# 12_4.net
KiCad netlist of a schematic drawn in Altium Designer
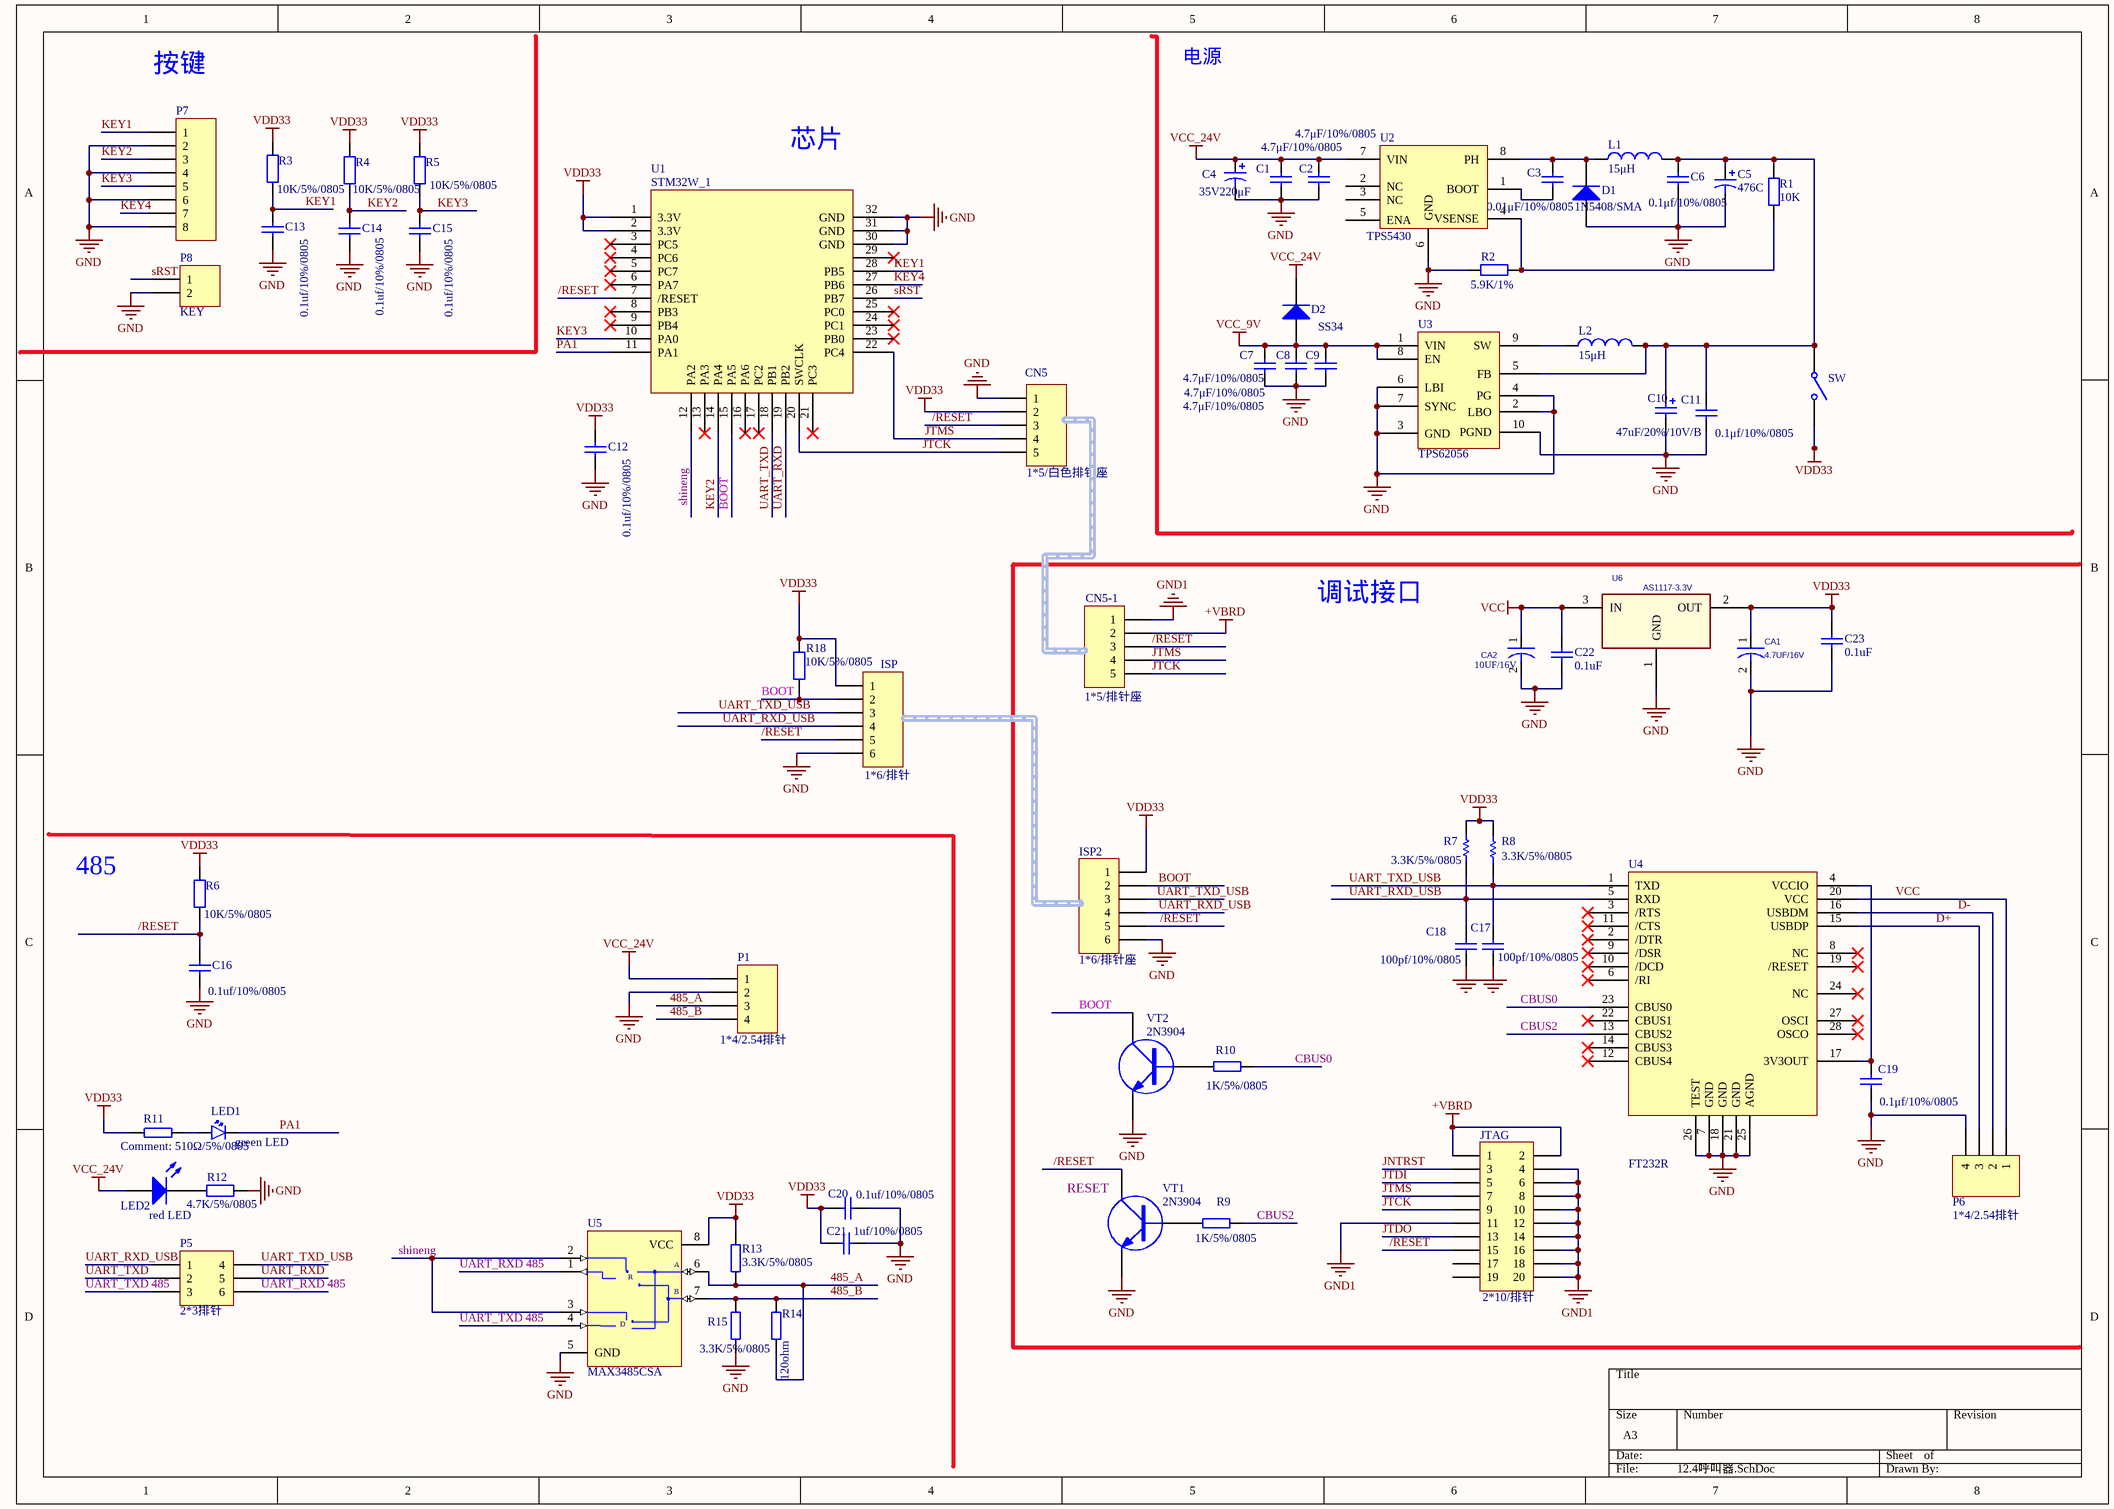
[diagram p0: 12.4呼叫器.SchDoc]

(export (version "E")
  (design (tool "Eeschema 10.0.6"))
  (components
    (comp (ref "C1")
      (value "4.7μF/10%/0805")
      (footprint "C-0805")
      (description "Capacitor")
      (fields (field (name "PUBLISHER") "Altium Limited"))
      (libsource (lib "Miscellaneous Devices") (part "Cap"))
    )
    (comp (ref "C2")
      (value "4.7μF/10%/0805")
      (footprint "C-0805")
      (description "Capacitor")
      (fields (field (name "PUBLISHER") "Altium Limited"))
      (libsource (lib "Miscellaneous Devices") (part "Cap"))
    )
    (comp (ref "C3")
      (value "0.01μF/10%/0805")
      (footprint "C-0805")
      (description "Capacitor")
      (fields (field (name "PUBLISHER") "Altium Limited"))
      (libsource (lib "Miscellaneous Devices") (part "Cap"))
    )
    (comp (ref "C4")
      (value "35V220μF")
      (footprint "CZ3.0/6.5")
      (description "Polarized Capacitor (Radial)")
      (fields (field (name "PUBLISHER") "Altium Limited"))
      (libsource (lib "Miscellaneous Devices") (part "Cap Pol1"))
    )
    (comp (ref "C5")
      (value "476C")
      (footprint "C-TAN-D")
      (description "Polarized Capacitor (Radial)")
      (fields (field (name "PUBLISHER") "Altium Limited"))
      (libsource (lib "Miscellaneous Devices") (part "Cap Pol1"))
    )
    (comp (ref "C6")
      (value "0.1μf/10%/0805")
      (footprint "C-0805")
      (description "Capacitor")
      (fields (field (name "PUBLISHER") "Altium Limited"))
      (libsource (lib "Miscellaneous Devices") (part "Cap"))
    )
    (comp (ref "C7")
      (value "4.7μF/10%/0805")
      (footprint "C-0805")
      (description "Capacitor")
      (fields (field (name "PUBLISHER") "Altium Limited"))
      (libsource (lib "Miscellaneous Devices") (part "Cap"))
    )
    (comp (ref "C8")
      (value "4.7μF/10%/0805")
      (footprint "C-0805")
      (description "Capacitor")
      (fields (field (name "PUBLISHER") "Altium Limited"))
      (libsource (lib "Miscellaneous Devices") (part "Cap"))
    )
    (comp (ref "C9")
      (value "4.7μF/10%/0805")
      (footprint "C-0805")
      (description "Capacitor")
      (fields (field (name "PUBLISHER") "Altium Limited"))
      (libsource (lib "Miscellaneous Devices") (part "Cap"))
    )
    (comp (ref "C10")
      (value "47uF/20%/10V/B")
      (footprint "C-TAN-B")
      (libsource (lib "浙江关西电机数据库") (part "CAP_polarity"))
    )
    (comp (ref "C11")
      (value "0.1μf/10%/0805")
      (footprint "C-0805")
      (description "Capacitor")
      (fields (field (name "PUBLISHER") "Altium Limited"))
      (libsource (lib "Miscellaneous Devices") (part "Cap"))
    )
    (comp (ref "C12")
      (value "0.1uf/10%/0805")
      (footprint "C-0805")
      (description "Capacitor")
      (fields (field (name "PUBLISHER") "Altium Limited"))
      (libsource (lib "Miscellaneous Devices") (part "Cap"))
    )
    (comp (ref "C13")
      (value "0.1uf/10%/0805")
      (footprint "C-0805")
      (description "Capacitor")
      (fields (field (name "PUBLISHER") "Altium Limited"))
      (libsource (lib "Miscellaneous Devices") (part "Cap"))
    )
    (comp (ref "C14")
      (value "0.1uf/10%/0805")
      (footprint "C-0805")
      (description "Capacitor")
      (fields (field (name "PUBLISHER") "Altium Limited"))
      (libsource (lib "Miscellaneous Devices") (part "Cap"))
    )
    (comp (ref "C15")
      (value "0.1uf/10%/0805")
      (footprint "C-0805")
      (description "Capacitor")
      (fields (field (name "PUBLISHER") "Altium Limited"))
      (libsource (lib "Miscellaneous Devices") (part "Cap"))
    )
    (comp (ref "C16")
      (value "0.1uf/10%/0805")
      (footprint "C-0805")
      (description "Capacitor")
      (fields (field (name "PUBLISHER") "Altium Limited"))
      (libsource (lib "Miscellaneous Devices") (part "Cap"))
    )
    (comp (ref "C17")
      (value "100pf/10%/0805")
      (footprint "C-0805")
      (description "Capacitor")
      (fields (field (name "PUBLISHER") "Altium Limited"))
      (libsource (lib "Miscellaneous Devices") (part "Cap"))
    )
    (comp (ref "C18")
      (value "100pf/10%/0805")
      (footprint "C-0805")
      (description "Capacitor")
      (fields (field (name "PUBLISHER") "Altium Limited"))
      (libsource (lib "Miscellaneous Devices") (part "Cap"))
    )
    (comp (ref "C19")
      (value "0.1μf/10%/0805")
      (footprint "C-0805")
      (description "Capacitor")
      (fields (field (name "PUBLISHER") "Altium Limited"))
      (libsource (lib "Miscellaneous Devices") (part "Cap"))
    )
    (comp (ref "C20")
      (value "0.1uf/10%/0805")
      (footprint "C-0805")
      (description "Capacitor")
      (fields (field (name "PUBLISHER") "Altium Limited"))
      (libsource (lib "Miscellaneous Devices") (part "Cap"))
    )
    (comp (ref "C21")
      (value "1uf/10%/0805")
      (footprint "C-0805")
      (description "Capacitor")
      (fields (field (name "PUBLISHER") "Altium Limited"))
      (libsource (lib "Miscellaneous Devices") (part "Cap"))
    )
    (comp (ref "C22")
      (value "0.1uF")
      (footprint "C0805")
      (description "Capacitor")
      (fields (field (name "PUBLISHER") "Altium Limited"))
      (libsource (lib "Miscellaneous Devices") (part "Cap"))
    )
    (comp (ref "C23")
      (value "0.1uF")
      (footprint "C0805")
      (description "Capacitor")
      (fields (field (name "PUBLISHER") "Altium Limited"))
      (libsource (lib "Miscellaneous Devices") (part "Cap"))
    )
    (comp (ref "CA1") (value "4.7UF/16V") (footprint "3528") (libsource (lib "v3") (part "ECAP")))
    (comp (ref "CA2") (value "10UF/16V") (footprint "3528") (libsource (lib "v3") (part "ECAP")))
    (comp (ref "CN5")
      (value "1*5/白色排针座")
      (footprint "PIN-S-2.54-1*5")
      (libsource (lib "SCHLIBRARIES") (part "Header1*5"))
    )
    (comp (ref "CN5-1")
      (value "1*5/排针座")
      (footprint "PIN-S-2.54-1*5")
      (libsource (lib "") (part "Header1*5_1"))
    )
    (comp (ref "D1")
      (value "1N5408/SMA")
      (footprint "SMA 2+")
      (description "3 Amp Medium Power Silicon Rectifier Diode")
      (fields (field (name "PUBLISHER") "Altium Limited"))
      (libsource (lib "Miscellaneous Devices") (part "Diode 1N5408"))
    )
    (comp (ref "D2")
      (value "SS34")
      (footprint "smb")
      (description "3 Amp Medium Power Silicon Rectifier Diode")
      (fields (field (name "PUBLISHER") "Altium Limited"))
      (libsource (lib "Miscellaneous Devices") (part "Diode 1N5408"))
    )
    (comp (ref "ISP") (value "1*6/排针") (footprint "PIN-S-2.54-1*6") (libsource (lib "") (part "Header1*6_1")))
    (comp (ref "ISP2")
      (value "1*6/排针座")
      (footprint "PIN-S-2.54-1*6")
      (libsource (lib "SCHLIBRARIES") (part "Header1*6"))
    )
    (comp (ref "JTAG")
      (value "2*10/排针")
      (footprint "IDC-20")
      (libsource (lib "SCHLIBRARIES") (part "Header2*10"))
    )
    (comp (ref "L1")
      (value "15μH")
      (footprint "GSDS104C2")
      (description "Inductor")
      (fields (field (name "PUBLISHER") "Altium Limited"))
      (libsource (lib "Miscellaneous Devices") (part "Inductor"))
    )
    (comp (ref "L2")
      (value "15μH")
      (footprint "GSDS104C2")
      (description "Inductor")
      (fields (field (name "PUBLISHER") "Altium Limited"))
      (libsource (lib "Miscellaneous Devices") (part "Inductor"))
    )
    (comp (ref "LED1") (value "green LED") (footprint "LED-φ3") (libsource (lib "Haze") (part "LED")))
    (comp (ref "LED2")
      (value "red LED")
      (footprint "LED-φ3")
      (description "Typical BLUE SiC LED")
      (fields (field (name "PUBLISHER") "Altium Limited"))
      (libsource (lib "Miscellaneous Devices") (part "LED3"))
    )
    (comp (ref "P1")
      (value "1*4/2.54排针")
      (footprint "PIN-S-2.54-1*4")
      (description "Header, 4-Pin")
      (fields (field (name "PUBLISHER") "Altium Limited"))
      (libsource (lib "Miscellaneous Connectors") (part "Header 4"))
    )
    (comp (ref "P5")
      (value "2*3排针")
      (footprint "HDR2X3_CEN")
      (description "Header, 3-Pin, Dual row")
      (fields (field (name "PUBLISHER") "Altium Limited"))
      (libsource (lib "Miscellaneous Connectors") (part "Header 3X2A"))
    )
    (comp (ref "P6")
      (value "1*4/2.54排针")
      (footprint "USB_B_90D")
      (description "Header, 4-Pin")
      (fields (field (name "PUBLISHER") "Altium Limited"))
      (libsource (lib "") (part "Header 4_1"))
    )
    (comp (ref "P7")
      (value "Header 8")
      (footprint "HDR1X8")
      (description "Header, 8-Pin")
      (fields (field (name "PUBLISHER") "Altium Limited"))
      (libsource (lib "Miscellaneous Connectors") (part "Header 8"))
    )
    (comp (ref "P8")
      (value "KEY")
      (footprint "KEY-DIP")
      (description "Header, 2-Pin")
      (fields (field (name "PUBLISHER") "Altium Limited"))
      (libsource (lib "Miscellaneous Connectors") (part "Header 2"))
    )
    (comp (ref "R1")
      (value "10K")
      (footprint "R-0805")
      (description "Resistor")
      (fields (field (name "PUBLISHER") "Altium Limited"))
      (libsource (lib "Miscellaneous Devices") (part "Res2"))
    )
    (comp (ref "R2")
      (value "5.9K/1%")
      (footprint "R-0805")
      (description "Resistor")
      (fields (field (name "PUBLISHER") "Altium Limited"))
      (libsource (lib "") (part "Res2_1"))
    )
    (comp (ref "R3")
      (value "10K/5%/0805")
      (footprint "R-0805")
      (description "Resistor")
      (fields (field (name "PUBLISHER") "Altium Limited"))
      (libsource (lib "Miscellaneous Devices") (part "Res2"))
    )
    (comp (ref "R4")
      (value "10K/5%/0805")
      (footprint "R-0805")
      (description "Resistor")
      (fields (field (name "PUBLISHER") "Altium Limited"))
      (libsource (lib "Miscellaneous Devices") (part "Res2"))
    )
    (comp (ref "R5")
      (value "10K/5%/0805")
      (footprint "R-0805")
      (description "Resistor")
      (fields (field (name "PUBLISHER") "Altium Limited"))
      (libsource (lib "Miscellaneous Devices") (part "Res2"))
    )
    (comp (ref "R6")
      (value "10K/5%/0805")
      (footprint "R-0805")
      (description "Resistor")
      (fields (field (name "PUBLISHER") "Altium Limited"))
      (libsource (lib "Miscellaneous Devices") (part "Res2"))
    )
    (comp (ref "R7")
      (value "3.3K/5%/0805")
      (footprint "R-0805")
      (libsource (lib "SCHLIBRARIES") (part "RES_1"))
    )
    (comp (ref "R8")
      (value "3.3K/5%/0805")
      (footprint "R-0805")
      (libsource (lib "SCHLIBRARIES") (part "RES_1"))
    )
    (comp (ref "R9")
      (value "1K/5%/0805")
      (footprint "R-0805")
      (description "R")
      (libsource (lib "Haze") (part "RES"))
    )
    (comp (ref "R10")
      (value "1K/5%/0805")
      (footprint "R-0805")
      (description "R")
      (libsource (lib "Haze") (part "RES"))
    )
    (comp (ref "R11")
      (value "510Ω/5%/0805")
      (footprint "R-0805")
      (description "R")
      (libsource (lib "Haze") (part "RES"))
    )
    (comp (ref "R12")
      (value "4.7K/5%/0805")
      (footprint "R-0805")
      (description "Resistor")
      (fields (field (name "PUBLISHER") "Altium Limited"))
      (libsource (lib "") (part "Res2_1"))
    )
    (comp (ref "R13")
      (value "3.3K/5%/0805")
      (footprint "R-0805")
      (description "R")
      (libsource (lib "Haze") (part "RES"))
    )
    (comp (ref "R14")
      (value "120ohm")
      (footprint "R-0805")
      (description "R")
      (libsource (lib "Haze") (part "RES"))
    )
    (comp (ref "R15")
      (value "3.3K/5%/0805")
      (footprint "R-0805")
      (description "R")
      (libsource (lib "Haze") (part "RES"))
    )
    (comp (ref "R18")
      (value "10K/5%/0805")
      (footprint "R-0805")
      (description "Resistor")
      (fields (field (name "PUBLISHER") "Altium Limited"))
      (libsource (lib "Miscellaneous Devices") (part "Res2"))
    )
    (comp (ref "SW")
      (value "SW-1")
      (footprint "PIN-S-2.54-1*2")
      (libsource (lib "SCHLIBRARIES") (part "SW-1"))
    )
    (comp (ref "U1")
      (value "STM32W_1")
      (footprint "STM32W108-3")
      (libsource (lib "STM32W108-3") (part "STM32W108-3"))
    )
    (comp (ref "U2") (value "TPS5430") (footprint "SO-G8") (libsource (lib "SCHLIBRARIES") (part "TPS5430")))
    (comp (ref "U3")
      (value "TPS62056")
      (footprint "MSOP-10")
      (libsource (lib "SCHLIBRARIES") (part "TPS62056"))
    )
    (comp (ref "U4") (value "FT232R") (footprint "SSOP-28") (libsource (lib "Haze") (part "FT232R")))
    (comp (ref "U5")
      (value "MAX3485CSA")
      (footprint "SO-G8")
      (description "Low-Power, Slew-Rate-Limited RS-485/RS-422 Transceiver")
      (fields (field (name "PUBLISHER") "Altium Limited"))
      (libsource (lib "Maxim Communication Transceiver") (part "MAX485CSA"))
    )
    (comp (ref "U6") (value "AS1117-3.3V") (libsource (lib "v3") (part "AS1117")))
    (comp (ref "VT1")
      (value "2N3904")
      (footprint "SOT23-3")
      (description "NPN Transistor")
      (libsource (lib "Haze") (part "NPN"))
    )
    (comp (ref "VT2")
      (value "2N3904")
      (footprint "SOT23-3")
      (description "NPN Transistor")
      (libsource (lib "Haze") (part "NPN"))
    )
  )
  (nets
    (net (code "1") (name "+VBRD") (class "Default")
      (node (ref "CN5-1") (pin "2") (pinfunction "2_2") (pintype "passive"))
      (node (ref "JTAG") (pin "1") (pinfunction "1_1") (pintype "passive"))
      (node (ref "JTAG") (pin "2") (pinfunction "2_2") (pintype "passive"))
    )
    (net (code "2") (name "/485_A") (class "Default")
      (node (ref "P1") (pin "3") (pinfunction "3_3") (pintype "passive"))
      (node (ref "R13") (pin "1") (pinfunction "1_1") (pintype "passive"))
      (node (ref "R14") (pin "2") (pinfunction "2_2") (pintype "passive"))
      (node (ref "U5") (pin "6") (pinfunction "A_6") (pintype "bidirectional"))
    )
    (net (code "3") (name "/485_B") (class "Default")
      (node (ref "P1") (pin "4") (pinfunction "4_4") (pintype "passive"))
      (node (ref "R14") (pin "1") (pinfunction "1_1") (pintype "passive"))
      (node (ref "R15") (pin "2") (pinfunction "2_2") (pintype "passive"))
      (node (ref "U5") (pin "7") (pinfunction "B_7") (pintype "bidirectional"))
    )
    (net (code "4") (name "/BOOT") (class "Default")
      (node (ref "ISP") (pin "2") (pinfunction "2_2") (pintype "passive"))
      (node (ref "ISP2") (pin "2") (pinfunction "2_2") (pintype "passive"))
      (node (ref "R18") (pin "1") (pinfunction "1_1") (pintype "passive"))
      (node (ref "U1") (pin "15") (pinfunction "PA5_15") (pintype "passive"))
      (node (ref "VT2") (pin "3") (pinfunction "C_3") (pintype "passive"))
    )
    (net (code "5") (name "/CBUS0") (class "Default")
      (node (ref "R10") (pin "2") (pinfunction "2_2") (pintype "passive"))
      (node (ref "U4") (pin "23") (pinfunction "CBUS0_23") (pintype "passive"))
    )
    (net (code "6") (name "/CBUS2") (class "Default")
      (node (ref "R9") (pin "2") (pinfunction "2_2") (pintype "passive"))
      (node (ref "U4") (pin "13") (pinfunction "CBUS2_13") (pintype "passive"))
    )
    (net (code "7") (name "/D+") (class "Default")
      (node (ref "P6") (pin "3") (pinfunction "3_3") (pintype "passive"))
      (node (ref "U4") (pin "15") (pinfunction "USBDP_15") (pintype "passive"))
    )
    (net (code "8") (name "/D-") (class "Default")
      (node (ref "P6") (pin "2") (pinfunction "2_2") (pintype "passive"))
      (node (ref "U4") (pin "16") (pinfunction "USBDM_16") (pintype "passive"))
    )
    (net (code "9") (name "/JNTRST") (class "Default")
      (node (ref "JTAG") (pin "3") (pinfunction "3_3") (pintype "passive"))
    )
    (net (code "10") (name "/JTCK") (class "Default")
      (node (ref "CN5") (pin "5") (pinfunction "5_5") (pintype "passive"))
      (node (ref "CN5-1") (pin "5") (pinfunction "5_5") (pintype "passive"))
      (node (ref "JTAG") (pin "9") (pinfunction "9_9") (pintype "passive"))
      (node (ref "U1") (pin "20") (pinfunction "SWCLK_20") (pintype "passive"))
    )
    (net (code "11") (name "/JTDI") (class "Default")
      (node (ref "JTAG") (pin "5") (pinfunction "5_5") (pintype "passive"))
    )
    (net (code "12") (name "/JTDO") (class "Default")
      (node (ref "JTAG") (pin "13") (pinfunction "13_13") (pintype "passive"))
    )
    (net (code "13") (name "/JTMS") (class "Default")
      (node (ref "CN5") (pin "4") (pinfunction "4_4") (pintype "passive"))
      (node (ref "CN5-1") (pin "4") (pinfunction "4_4") (pintype "passive"))
      (node (ref "JTAG") (pin "7") (pinfunction "7_7") (pintype "passive"))
      (node (ref "U1") (pin "22") (pinfunction "PC4_22") (pintype "passive"))
    )
    (net (code "14") (name "/KEY1") (class "Default")
      (node (ref "C13") (pin "2") (pinfunction "2_2") (pintype "passive"))
      (node (ref "P7") (pin "1") (pinfunction "1_1") (pintype "passive"))
      (node (ref "R3") (pin "1") (pinfunction "1_1") (pintype "passive"))
      (node (ref "U1") (pin "28") (pinfunction "PB5_28") (pintype "passive"))
    )
    (net (code "15") (name "/KEY2") (class "Default")
      (node (ref "C14") (pin "2") (pinfunction "2_2") (pintype "passive"))
      (node (ref "P7") (pin "3") (pinfunction "3_3") (pintype "passive"))
      (node (ref "R4") (pin "1") (pinfunction "1_1") (pintype "passive"))
      (node (ref "U1") (pin "14") (pinfunction "PA4_14") (pintype "passive"))
    )
    (net (code "16") (name "/KEY3") (class "Default")
      (node (ref "C15") (pin "2") (pinfunction "2_2") (pintype "passive"))
      (node (ref "P7") (pin "5") (pinfunction "5_5") (pintype "passive"))
      (node (ref "R5") (pin "1") (pinfunction "1_1") (pintype "passive"))
      (node (ref "U1") (pin "10") (pinfunction "PA0_10") (pintype "passive"))
    )
    (net (code "17") (name "/KEY4") (class "Default")
      (node (ref "P7") (pin "7") (pinfunction "7_7") (pintype "passive"))
      (node (ref "U1") (pin "27") (pinfunction "PB6_27") (pintype "passive"))
    )
    (net (code "18") (name "/PA1") (class "Default")
      (node (ref "LED1") (pin "2") (pinfunction "K_2") (pintype "passive"))
      (node (ref "U1") (pin "11") (pinfunction "PA1_11") (pintype "passive"))
    )
    (net (code "19") (name "/UART_RXD") (class "Default")
      (node (ref "P5") (pin "5") (pinfunction "5_5") (pintype "passive"))
      (node (ref "U1") (pin "19") (pinfunction "PB2_19") (pintype "passive"))
    )
    (net (code "20") (name "/UART_RXD 485") (class "Default")
      (node (ref "P5") (pin "6") (pinfunction "6_6") (pintype "passive"))
      (node (ref "U5") (pin "1") (pinfunction "RO_1") (pintype "output"))
    )
    (net (code "21") (name "/UART_RXD_USB") (class "Default")
      (node (ref "C18") (pin "2") (pinfunction "2_2") (pintype "passive"))
      (node (ref "ISP") (pin "4") (pinfunction "4_4") (pintype "passive"))
      (node (ref "ISP2") (pin "4") (pinfunction "4_4") (pintype "passive"))
      (node (ref "P5") (pin "1") (pinfunction "1_1") (pintype "passive"))
      (node (ref "R7") (pin "1") (pinfunction "1_1") (pintype "passive"))
      (node (ref "U4") (pin "5") (pinfunction "RXD_5") (pintype "passive"))
    )
    (net (code "22") (name "/UART_TXD") (class "Default")
      (node (ref "P5") (pin "2") (pinfunction "2_2") (pintype "passive"))
      (node (ref "U1") (pin "18") (pinfunction "PB1_18") (pintype "passive"))
    )
    (net (code "23") (name "/UART_TXD 485") (class "Default")
      (node (ref "P5") (pin "3") (pinfunction "3_3") (pintype "passive"))
      (node (ref "U5") (pin "4") (pinfunction "DI_4") (pintype "input"))
    )
    (net (code "24") (name "/UART_TXD_USB") (class "Default")
      (node (ref "C17") (pin "2") (pinfunction "2_2") (pintype "passive"))
      (node (ref "ISP") (pin "3") (pinfunction "3_3") (pintype "passive"))
      (node (ref "ISP2") (pin "3") (pinfunction "3_3") (pintype "passive"))
      (node (ref "P5") (pin "4") (pinfunction "4_4") (pintype "passive"))
      (node (ref "R8") (pin "1") (pinfunction "1_1") (pintype "passive"))
      (node (ref "U4") (pin "1") (pinfunction "TXD_1") (pintype "passive"))
    )
    (net (code "25") (name "/sRST") (class "Default")
      (node (ref "P8") (pin "1") (pinfunction "1_1") (pintype "passive"))
      (node (ref "U1") (pin "26") (pinfunction "PB7_26") (pintype "passive"))
    )
    (net (code "26") (name "/shineng") (class "Default")
      (node (ref "U1") (pin "12") (pinfunction "PA2_12") (pintype "passive"))
      (node (ref "U5") (pin "2") (pinfunction "~{RE}_2") (pintype "input"))
      (node (ref "U5") (pin "3") (pinfunction "DE_3") (pintype "input"))
    )
    (net (code "27") (name "/{slash}RESET") (class "Default")
      (node (ref "C16") (pin "2") (pinfunction "2_2") (pintype "passive"))
      (node (ref "CN5") (pin "3") (pinfunction "3_3") (pintype "passive"))
      (node (ref "CN5-1") (pin "3") (pinfunction "3_3") (pintype "passive"))
      (node (ref "ISP") (pin "5") (pinfunction "5_5") (pintype "passive"))
      (node (ref "ISP2") (pin "5") (pinfunction "5_5") (pintype "passive"))
      (node (ref "JTAG") (pin "15") (pinfunction "15_15") (pintype "passive"))
      (node (ref "R6") (pin "1") (pinfunction "1_1") (pintype "passive"))
      (node (ref "U1") (pin "7") (pinfunction "/RESET_7") (pintype "passive"))
      (node (ref "VT1") (pin "3") (pinfunction "C_3") (pintype "passive"))
    )
    (net (code "28") (name "GND") (class "Default")
      (node (ref "C1") (pin "1") (pinfunction "1_1") (pintype "passive"))
      (node (ref "C10") (pin "2") (pinfunction "2_2") (pintype "passive"))
      (node (ref "C11") (pin "1") (pinfunction "1_1") (pintype "passive"))
      (node (ref "C12") (pin "1") (pinfunction "1_1") (pintype "passive"))
      (node (ref "C13") (pin "1") (pinfunction "1_1") (pintype "passive"))
      (node (ref "C14") (pin "1") (pinfunction "1_1") (pintype "passive"))
      (node (ref "C15") (pin "1") (pinfunction "1_1") (pintype "passive"))
      (node (ref "C16") (pin "1") (pinfunction "1_1") (pintype "passive"))
      (node (ref "C17") (pin "1") (pinfunction "1_1") (pintype "passive"))
      (node (ref "C18") (pin "1") (pinfunction "1_1") (pintype "passive"))
      (node (ref "C19") (pin "1") (pinfunction "1_1") (pintype "passive"))
      (node (ref "C2") (pin "1") (pinfunction "1_1") (pintype "passive"))
      (node (ref "C20") (pin "1") (pinfunction "1_1") (pintype "passive"))
      (node (ref "C21") (pin "1") (pinfunction "1_1") (pintype "passive"))
      (node (ref "C22") (pin "1") (pinfunction "1_1") (pintype "passive"))
      (node (ref "C23") (pin "1") (pinfunction "1_1") (pintype "passive"))
      (node (ref "C4") (pin "2") (pinfunction "2_2") (pintype "passive"))
      (node (ref "C5") (pin "2") (pinfunction "2_2") (pintype "passive"))
      (node (ref "C6") (pin "1") (pinfunction "1_1") (pintype "passive"))
      (node (ref "C7") (pin "1") (pinfunction "1_1") (pintype "passive"))
      (node (ref "C8") (pin "1") (pinfunction "1_1") (pintype "passive"))
      (node (ref "C9") (pin "1") (pinfunction "1_1") (pintype "passive"))
      (node (ref "CA1") (pin "2") (pinfunction "2_2") (pintype "passive"))
      (node (ref "CA2") (pin "2") (pinfunction "2_2") (pintype "passive"))
      (node (ref "CN5") (pin "1") (pinfunction "1_1") (pintype "passive"))
      (node (ref "D1") (pin "1") (pinfunction "A_1") (pintype "passive"))
      (node (ref "ISP") (pin "6") (pinfunction "6_6") (pintype "passive"))
      (node (ref "ISP2") (pin "6") (pinfunction "6_6") (pintype "passive"))
      (node (ref "P1") (pin "2") (pinfunction "2_2") (pintype "passive"))
      (node (ref "P6") (pin "4") (pinfunction "4_4") (pintype "passive"))
      (node (ref "P7") (pin "2") (pinfunction "2_2") (pintype "passive"))
      (node (ref "P7") (pin "4") (pinfunction "4_4") (pintype "passive"))
      (node (ref "P7") (pin "6") (pinfunction "6_6") (pintype "passive"))
      (node (ref "P7") (pin "8") (pinfunction "8_8") (pintype "passive"))
      (node (ref "P8") (pin "2") (pinfunction "2_2") (pintype "passive"))
      (node (ref "R12") (pin "1") (pinfunction "1_1") (pintype "passive"))
      (node (ref "R15") (pin "1") (pinfunction "1_1") (pintype "passive"))
      (node (ref "R2") (pin "2") (pinfunction "2_2") (pintype "passive"))
      (node (ref "U1") (pin "30") (pinfunction "GND_30") (pintype "passive"))
      (node (ref "U1") (pin "31") (pinfunction "GND_31") (pintype "passive"))
      (node (ref "U1") (pin "32") (pinfunction "GND_32") (pintype "passive"))
      (node (ref "U2") (pin "6") (pinfunction "GND_6") (pintype "passive"))
      (node (ref "U3") (pin "10") (pinfunction "PGND_10") (pintype "passive"))
      (node (ref "U3") (pin "2") (pinfunction "LBO_2") (pintype "passive"))
      (node (ref "U3") (pin "3") (pinfunction "GND_3") (pintype "passive"))
      (node (ref "U3") (pin "4") (pinfunction "PG_4") (pintype "passive"))
      (node (ref "U3") (pin "6") (pinfunction "LBI_6") (pintype "passive"))
      (node (ref "U3") (pin "7") (pinfunction "SYNC_7") (pintype "passive"))
      (node (ref "U4") (pin "18") (pinfunction "GND_18") (pintype "passive"))
      (node (ref "U4") (pin "21") (pinfunction "GND_21") (pintype "passive"))
      (node (ref "U4") (pin "25") (pinfunction "AGND_25") (pintype "passive"))
      (node (ref "U4") (pin "26") (pinfunction "TEST_26") (pintype "passive"))
      (node (ref "U4") (pin "7") (pinfunction "GND_7") (pintype "passive"))
      (node (ref "U5") (pin "5") (pinfunction "GND_5") (pintype "power_in"))
      (node (ref "U6") (pin "1") (pinfunction "GND_1") (pintype "passive"))
      (node (ref "VT1") (pin "2") (pinfunction "E_2") (pintype "passive"))
      (node (ref "VT2") (pin "2") (pinfunction "E_2") (pintype "passive"))
    )
    (net (code "29") (name "GND1") (class "Default")
      (node (ref "CN5-1") (pin "1") (pinfunction "1_1") (pintype "passive"))
      (node (ref "JTAG") (pin "10") (pinfunction "10_10") (pintype "passive"))
      (node (ref "JTAG") (pin "11") (pinfunction "11_11") (pintype "passive"))
      (node (ref "JTAG") (pin "12") (pinfunction "12_12") (pintype "passive"))
      (node (ref "JTAG") (pin "14") (pinfunction "14_14") (pintype "passive"))
      (node (ref "JTAG") (pin "16") (pinfunction "16_16") (pintype "passive"))
      (node (ref "JTAG") (pin "18") (pinfunction "18_18") (pintype "passive"))
      (node (ref "JTAG") (pin "20") (pinfunction "20_20") (pintype "passive"))
      (node (ref "JTAG") (pin "4") (pinfunction "4_4") (pintype "passive"))
      (node (ref "JTAG") (pin "6") (pinfunction "6_6") (pintype "passive"))
      (node (ref "JTAG") (pin "8") (pinfunction "8_8") (pintype "passive"))
    )
    (net (code "30") (name "Net-(D1-K)") (class "Default")
      (node (ref "C3") (pin "2") (pinfunction "2_2") (pintype "passive"))
      (node (ref "D1") (pin "2") (pinfunction "K_2") (pintype "passive"))
      (node (ref "L1") (pin "1") (pinfunction "1_1") (pintype "passive"))
      (node (ref "U2") (pin "8") (pinfunction "PH_8") (pintype "passive"))
    )
    (net (code "31") (name "Net-(LED1-A)") (class "Default")
      (node (ref "LED1") (pin "1") (pinfunction "A_1") (pintype "passive"))
      (node (ref "R11") (pin "2") (pinfunction "2_2") (pintype "passive"))
    )
    (net (code "32") (name "Net-(LED2-K)") (class "Default")
      (node (ref "LED2") (pin "2") (pinfunction "K_2") (pintype "passive"))
      (node (ref "R12") (pin "2") (pinfunction "2_2") (pintype "passive"))
    )
    (net (code "33") (name "Net-(U2-BOOT)") (class "Default")
      (node (ref "C3") (pin "1") (pinfunction "1_1") (pintype "passive"))
      (node (ref "U2") (pin "1") (pinfunction "BOOT_1") (pintype "passive"))
    )
    (net (code "34") (name "Net-(U2-VSENSE)") (class "Default")
      (node (ref "R1") (pin "1") (pinfunction "1_1") (pintype "passive"))
      (node (ref "R2") (pin "1") (pinfunction "1_1") (pintype "passive"))
      (node (ref "U2") (pin "4") (pinfunction "VSENSE_4") (pintype "passive"))
    )
    (net (code "35") (name "Net-(U3-FB)") (class "Default")
      (node (ref "C10") (pin "1") (pinfunction "1_1") (pintype "passive"))
      (node (ref "C11") (pin "2") (pinfunction "2_2") (pintype "passive"))
      (node (ref "C5") (pin "1") (pinfunction "1_1") (pintype "passive"))
      (node (ref "C6") (pin "2") (pinfunction "2_2") (pintype "passive"))
      (node (ref "L1") (pin "2") (pinfunction "2_2") (pintype "passive"))
      (node (ref "L2") (pin "2") (pinfunction "2_2") (pintype "passive"))
      (node (ref "R1") (pin "2") (pinfunction "2_2") (pintype "passive"))
      (node (ref "SW") (pin "1") (pinfunction "1_1") (pintype "passive"))
      (node (ref "U3") (pin "5") (pinfunction "FB_5") (pintype "passive"))
    )
    (net (code "36") (name "Net-(U3-SW)") (class "Default")
      (node (ref "L2") (pin "1") (pinfunction "1_1") (pintype "passive"))
      (node (ref "U3") (pin "9") (pinfunction "SW_9") (pintype "passive"))
    )
    (net (code "37") (name "Net-(U4-3V3OUT)") (class "Default")
      (node (ref "C19") (pin "2") (pinfunction "2_2") (pintype "passive"))
      (node (ref "U4") (pin "17") (pinfunction "3V3OUT_17") (pintype "passive"))
      (node (ref "U4") (pin "4") (pinfunction "VCCIO_4") (pintype "passive"))
    )
    (net (code "38") (name "Net-(VT1-B)") (class "Default")
      (node (ref "R9") (pin "1") (pinfunction "1_1") (pintype "passive"))
      (node (ref "VT1") (pin "1") (pinfunction "B_1") (pintype "passive"))
    )
    (net (code "39") (name "Net-(VT2-B)") (class "Default")
      (node (ref "R10") (pin "1") (pinfunction "1_1") (pintype "passive"))
      (node (ref "VT2") (pin "1") (pinfunction "B_1") (pintype "passive"))
    )
    (net (code "40") (name "VCC") (class "Default")
      (node (ref "C22") (pin "2") (pinfunction "2_2") (pintype "passive"))
      (node (ref "CA2") (pin "1") (pinfunction "1_1") (pintype "passive"))
      (node (ref "P6") (pin "1") (pinfunction "1_1") (pintype "passive"))
      (node (ref "U4") (pin "20") (pinfunction "VCC_20") (pintype "passive"))
      (node (ref "U6") (pin "3") (pinfunction "IN_3") (pintype "passive"))
    )
    (net (code "41") (name "VCC_9V") (class "Default")
      (node (ref "C7") (pin "2") (pinfunction "2_2") (pintype "passive"))
      (node (ref "C8") (pin "2") (pinfunction "2_2") (pintype "passive"))
      (node (ref "C9") (pin "2") (pinfunction "2_2") (pintype "passive"))
      (node (ref "D2") (pin "1") (pinfunction "A_1") (pintype "passive"))
      (node (ref "U3") (pin "1") (pinfunction "VIN_1") (pintype "passive"))
      (node (ref "U3") (pin "8") (pinfunction "EN_8") (pintype "passive"))
    )
    (net (code "42") (name "VCC_24V") (class "Default")
      (node (ref "C1") (pin "2") (pinfunction "2_2") (pintype "passive"))
      (node (ref "C2") (pin "2") (pinfunction "2_2") (pintype "passive"))
      (node (ref "C4") (pin "1") (pinfunction "1_1") (pintype "passive"))
      (node (ref "D2") (pin "2") (pinfunction "K_2") (pintype "passive"))
      (node (ref "LED2") (pin "1") (pinfunction "A_1") (pintype "passive"))
      (node (ref "P1") (pin "1") (pinfunction "1_1") (pintype "passive"))
      (node (ref "U2") (pin "7") (pinfunction "VIN_7") (pintype "passive"))
    )
    (net (code "43") (name "VDD33") (class "Default")
      (node (ref "C12") (pin "2") (pinfunction "2_2") (pintype "passive"))
      (node (ref "C20") (pin "2") (pinfunction "2_2") (pintype "passive"))
      (node (ref "C21") (pin "2") (pinfunction "2_2") (pintype "passive"))
      (node (ref "C23") (pin "2") (pinfunction "2_2") (pintype "passive"))
      (node (ref "CA1") (pin "1") (pinfunction "1_1") (pintype "passive"))
      (node (ref "CN5") (pin "2") (pinfunction "2_2") (pintype "passive"))
      (node (ref "ISP") (pin "1") (pinfunction "1_1") (pintype "passive"))
      (node (ref "ISP2") (pin "1") (pinfunction "1_1") (pintype "passive"))
      (node (ref "R11") (pin "1") (pinfunction "1_1") (pintype "passive"))
      (node (ref "R13") (pin "2") (pinfunction "2_2") (pintype "passive"))
      (node (ref "R18") (pin "2") (pinfunction "2_2") (pintype "passive"))
      (node (ref "R3") (pin "2") (pinfunction "2_2") (pintype "passive"))
      (node (ref "R4") (pin "2") (pinfunction "2_2") (pintype "passive"))
      (node (ref "R5") (pin "2") (pinfunction "2_2") (pintype "passive"))
      (node (ref "R6") (pin "2") (pinfunction "2_2") (pintype "passive"))
      (node (ref "R7") (pin "2") (pinfunction "2_2") (pintype "passive"))
      (node (ref "R8") (pin "2") (pinfunction "2_2") (pintype "passive"))
      (node (ref "SW") (pin "2") (pinfunction "2_2") (pintype "passive"))
      (node (ref "U1") (pin "1") (pinfunction "3.3V_1") (pintype "passive"))
      (node (ref "U1") (pin "2") (pinfunction "3.3V_2") (pintype "passive"))
      (node (ref "U5") (pin "8") (pinfunction "VCC_8") (pintype "power_in"))
      (node (ref "U6") (pin "2") (pinfunction "OUT_2") (pintype "passive"))
    )
    (net (code "44") (name "unconnected-(JTAG-Pad17)") (class "Default")
      (node (ref "JTAG") (pin "17") (pinfunction "17_17") (pintype "passive"))
    )
    (net (code "45") (name "unconnected-(JTAG-Pad19)") (class "Default")
      (node (ref "JTAG") (pin "19") (pinfunction "19_19") (pintype "passive"))
    )
    (net (code "46") (name "unconnected-(U1-PA3-Pad13)") (class "Default")
      (node (ref "U1") (pin "13") (pinfunction "PA3_13") (pintype "passive+no_connect"))
    )
    (net (code "47") (name "unconnected-(U1-PA6-Pad16)") (class "Default")
      (node (ref "U1") (pin "16") (pinfunction "PA6_16") (pintype "passive+no_connect"))
    )
    (net (code "48") (name "unconnected-(U1-PA7-Pad6)") (class "Default")
      (node (ref "U1") (pin "6") (pinfunction "PA7_6") (pintype "passive+no_connect"))
    )
    (net (code "49") (name "unconnected-(U1-PB0-Pad23)") (class "Default")
      (node (ref "U1") (pin "23") (pinfunction "PB0_23") (pintype "passive+no_connect"))
    )
    (net (code "50") (name "unconnected-(U1-PB3-Pad8)") (class "Default")
      (node (ref "U1") (pin "8") (pinfunction "PB3_8") (pintype "passive+no_connect"))
    )
    (net (code "51") (name "unconnected-(U1-PB4-Pad9)") (class "Default")
      (node (ref "U1") (pin "9") (pinfunction "PB4_9") (pintype "passive+no_connect"))
    )
    (net (code "52") (name "unconnected-(U1-PC0-Pad25)") (class "Default")
      (node (ref "U1") (pin "25") (pinfunction "PC0_25") (pintype "passive+no_connect"))
    )
    (net (code "53") (name "unconnected-(U1-PC1-Pad24)") (class "Default")
      (node (ref "U1") (pin "24") (pinfunction "PC1_24") (pintype "passive+no_connect"))
    )
    (net (code "54") (name "unconnected-(U1-PC2-Pad17)") (class "Default")
      (node (ref "U1") (pin "17") (pinfunction "PC2_17") (pintype "passive+no_connect"))
    )
    (net (code "55") (name "unconnected-(U1-PC3-Pad21)") (class "Default")
      (node (ref "U1") (pin "21") (pinfunction "PC3_21") (pintype "passive+no_connect"))
    )
    (net (code "56") (name "unconnected-(U1-PC5-Pad3)") (class "Default")
      (node (ref "U1") (pin "3") (pinfunction "PC5_3") (pintype "passive+no_connect"))
    )
    (net (code "57") (name "unconnected-(U1-PC6-Pad4)") (class "Default")
      (node (ref "U1") (pin "4") (pinfunction "PC6_4") (pintype "passive+no_connect"))
    )
    (net (code "58") (name "unconnected-(U1-PC7-Pad5)") (class "Default")
      (node (ref "U1") (pin "5") (pinfunction "PC7_5") (pintype "passive+no_connect"))
    )
    (net (code "59") (name "unconnected-(U1-Pad29)") (class "Default")
      (node (ref "U1") (pin "29") (pintype "passive+no_connect"))
    )
    (net (code "60") (name "unconnected-(U2-ENA-Pad5)") (class "Default")
      (node (ref "U2") (pin "5") (pinfunction "ENA_5") (pintype "passive"))
    )
    (net (code "61") (name "unconnected-(U2-NC-Pad2)") (class "Default")
      (node (ref "U2") (pin "2") (pinfunction "NC_2") (pintype "passive"))
    )
    (net (code "62") (name "unconnected-(U2-NC-Pad3)") (class "Default")
      (node (ref "U2") (pin "3") (pinfunction "NC_3") (pintype "passive"))
    )
    (net (code "63") (name "unconnected-(U4-CBUS1-Pad22)") (class "Default")
      (node (ref "U4") (pin "22") (pinfunction "CBUS1_22") (pintype "passive+no_connect"))
    )
    (net (code "64") (name "unconnected-(U4-CBUS3-Pad14)") (class "Default")
      (node (ref "U4") (pin "14") (pinfunction "CBUS3_14") (pintype "passive+no_connect"))
    )
    (net (code "65") (name "unconnected-(U4-CBUS4-Pad12)") (class "Default")
      (node (ref "U4") (pin "12") (pinfunction "CBUS4_12") (pintype "passive+no_connect"))
    )
    (net (code "66") (name "unconnected-(U4-NC-Pad8)") (class "Default")
      (node (ref "U4") (pin "8") (pinfunction "NC_8") (pintype "passive+no_connect"))
    )
    (net (code "67") (name "unconnected-(U4-NC-Pad24)") (class "Default")
      (node (ref "U4") (pin "24") (pinfunction "NC_24") (pintype "passive+no_connect"))
    )
    (net (code "68") (name "unconnected-(U4-OSCI-Pad27)") (class "Default")
      (node (ref "U4") (pin "27") (pinfunction "OSCI_27") (pintype "passive+no_connect"))
    )
    (net (code "69") (name "unconnected-(U4-OSCO-Pad28)") (class "Default")
      (node (ref "U4") (pin "28") (pinfunction "OSCO_28") (pintype "passive+no_connect"))
    )
    (net (code "70") (name "unconnected-(U4-{slash}CTS-Pad11)") (class "Default")
      (node (ref "U4") (pin "11") (pinfunction "/CTS_11") (pintype "passive+no_connect"))
    )
    (net (code "71") (name "unconnected-(U4-{slash}DCD-Pad10)") (class "Default")
      (node (ref "U4") (pin "10") (pinfunction "/DCD_10") (pintype "passive+no_connect"))
    )
    (net (code "72") (name "unconnected-(U4-{slash}DSR-Pad9)") (class "Default")
      (node (ref "U4") (pin "9") (pinfunction "/DSR_9") (pintype "passive+no_connect"))
    )
    (net (code "73") (name "unconnected-(U4-{slash}DTR-Pad2)") (class "Default")
      (node (ref "U4") (pin "2") (pinfunction "/DTR_2") (pintype "passive+no_connect"))
    )
    (net (code "74") (name "unconnected-(U4-{slash}RESET-Pad19)") (class "Default")
      (node (ref "U4") (pin "19") (pinfunction "/RESET_19") (pintype "passive+no_connect"))
    )
    (net (code "75") (name "unconnected-(U4-{slash}RI-Pad6)") (class "Default")
      (node (ref "U4") (pin "6") (pinfunction "/RI_6") (pintype "passive+no_connect"))
    )
    (net (code "76") (name "unconnected-(U4-{slash}RTS-Pad3)") (class "Default")
      (node (ref "U4") (pin "3") (pinfunction "/RTS_3") (pintype "passive+no_connect"))
    )
  )
)
